# Root.net
KiCad netlist of a schematic drawn in Altium Designer
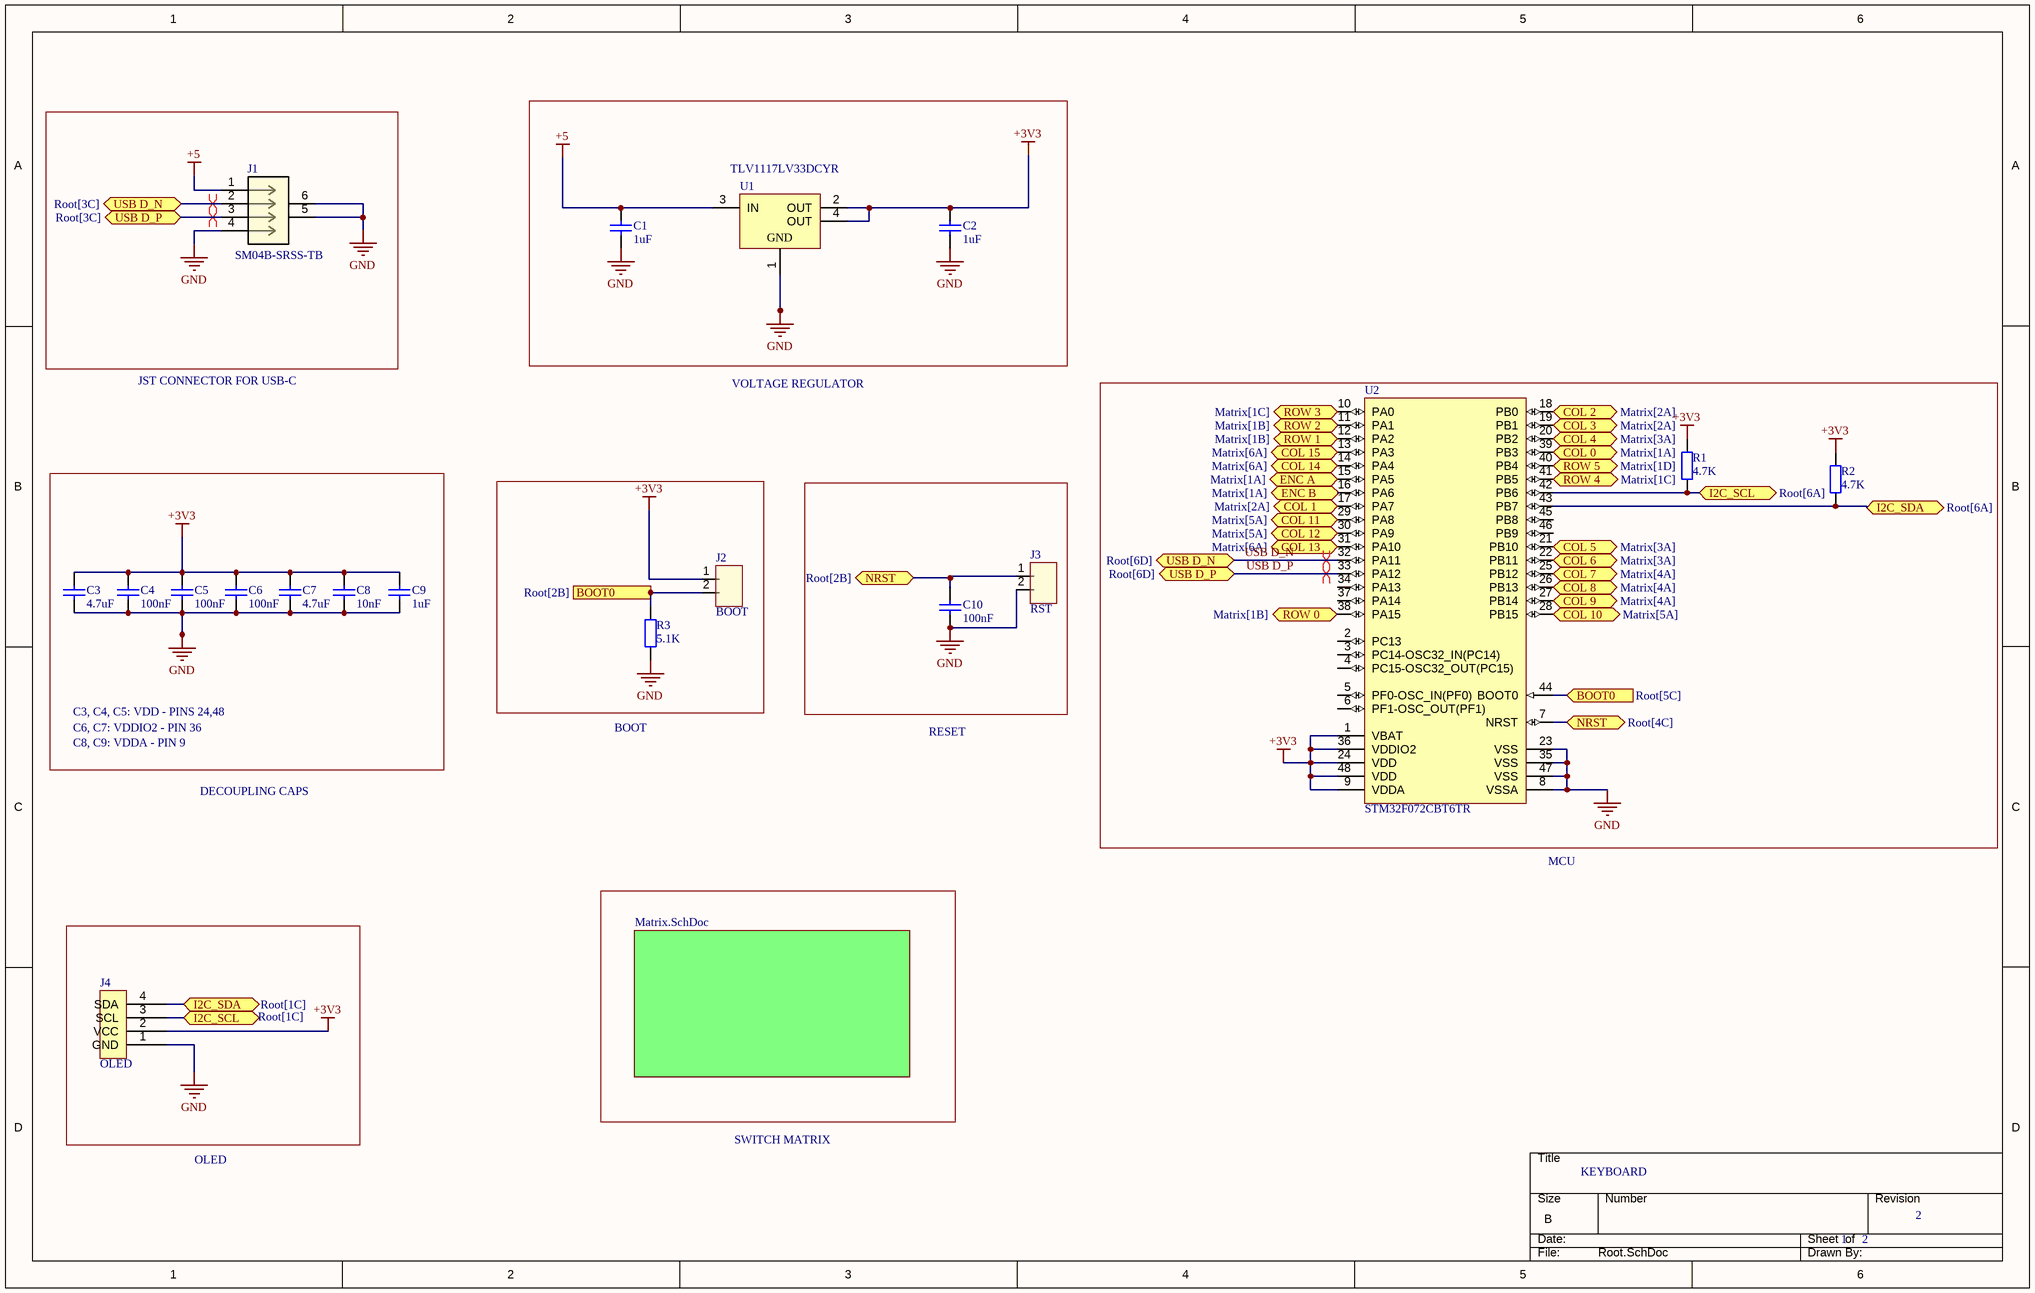
[diagram p0: Root.SchDoc]

(export (version "E")
  (design (tool "Eeschema 10.0.6"))
  (components
    (comp (ref "C1")
      (value "1uF")
      (footprint "C0805")
      (description "Capacitor")
      (fields (field (name "Comment") "Cap") (field (name "PUBLISHER") "Altium Limited"))
      (libsource (lib "Miscellaneous Devices") (part "Cap"))
    )
    (comp (ref "C2")
      (value "1uF")
      (footprint "C0805")
      (description "Capacitor")
      (fields (field (name "Comment") "Cap") (field (name "PUBLISHER") "Altium Limited"))
      (libsource (lib "Miscellaneous Devices") (part "Cap"))
    )
    (comp (ref "C3")
      (value "4.7uF")
      (footprint "C0805")
      (description "Capacitor")
      (fields (field (name "Comment") "Cap") (field (name "PUBLISHER") "Altium Limited"))
      (libsource (lib "Miscellaneous Devices") (part "Cap"))
    )
    (comp (ref "C4")
      (value "100nF")
      (footprint "C0805")
      (description "Capacitor")
      (fields (field (name "Comment") "Cap") (field (name "PUBLISHER") "Altium Limited"))
      (libsource (lib "Miscellaneous Devices") (part "Cap"))
    )
    (comp (ref "C5")
      (value "100nF")
      (footprint "C0805")
      (description "Capacitor")
      (fields (field (name "Comment") "Cap") (field (name "PUBLISHER") "Altium Limited"))
      (libsource (lib "Miscellaneous Devices") (part "Cap"))
    )
    (comp (ref "C6")
      (value "100nF")
      (footprint "C0805")
      (description "Capacitor")
      (fields (field (name "Comment") "Cap") (field (name "PUBLISHER") "Altium Limited"))
      (libsource (lib "Miscellaneous Devices") (part "Cap"))
    )
    (comp (ref "C7")
      (value "4.7uF")
      (footprint "C0805")
      (description "Capacitor")
      (fields (field (name "Comment") "Cap") (field (name "PUBLISHER") "Altium Limited"))
      (libsource (lib "Miscellaneous Devices") (part "Cap"))
    )
    (comp (ref "C8")
      (value "10nF")
      (footprint "C0805")
      (description "Capacitor")
      (fields (field (name "Comment") "Cap") (field (name "PUBLISHER") "Altium Limited"))
      (libsource (lib "Miscellaneous Devices") (part "Cap"))
    )
    (comp (ref "C9")
      (value "1uF")
      (footprint "C0805")
      (description "Capacitor")
      (fields (field (name "Comment") "Cap") (field (name "PUBLISHER") "Altium Limited"))
      (libsource (lib "Miscellaneous Devices") (part "Cap"))
    )
    (comp (ref "C10")
      (value "100nF")
      (footprint "C0805")
      (description "Capacitor")
      (fields (field (name "Comment") "Cap") (field (name "PUBLISHER") "Altium Limited"))
      (libsource (lib "Miscellaneous Devices") (part "Cap"))
    )
    (comp (ref "J1")
      (value "SM04B-SRSS-TB")
      (footprint "JST-SR-4")
      (description "No Description Available")
      (libsource (lib "SM04B-SRSS-TB") (part "SM04B-SRSS-TB"))
    )
    (comp (ref "J2")
      (value "BOOT")
      (footprint "HDR_1X2")
      (libsource (lib "Daniel Hai") (part "Copy of HDRMINI_M_1X2"))
    )
    (comp (ref "J3")
      (value "RST")
      (footprint "HDR_1X2")
      (libsource (lib "Daniel Hai") (part "Copy of HDRMINI_M_1X2"))
    )
    (comp (ref "J4")
      (value "OLED")
      (footprint "SSD1306-0.91-OLED-4pin-128x32")
      (description "4 pin header")
      (libsource (lib "Daniel Hai") (part "GND"))
    )
    (comp (ref "R1")
      (value "4.7K")
      (footprint "6-0805_M")
      (description "Resistor")
      (fields (field (name "Comment") "Res2") (field (name "PUBLISHER") "Altium Limited"))
      (libsource (lib "Miscellaneous Devices") (part "Res2"))
    )
    (comp (ref "R2")
      (value "4.7K")
      (footprint "6-0805_M")
      (description "Resistor")
      (fields (field (name "Comment") "Res2") (field (name "PUBLISHER") "Altium Limited"))
      (libsource (lib "Miscellaneous Devices") (part "Res2"))
    )
    (comp (ref "R3")
      (value "5.1K")
      (footprint "6-0805_M")
      (description "Resistor")
      (fields (field (name "Comment") "Res2") (field (name "PUBLISHER") "Altium Limited"))
      (libsource (lib "Miscellaneous Devices") (part "Res2"))
    )
    (comp (ref "U1")
      (value "TLV1117LV33DCYR")
      (footprint "DCY0004A_M")
      (fields (field (name "MANUFACTURER") "Texas Instruments"))
      (libsource (lib "Altium Content Vault") (part "TI-TLV1117LV33DCY4"))
    )
    (comp (ref "U2")
      (value "STM32F072CBT6TR")
      (footprint "STM-LQFP48_M")
      (libsource (lib "Altium Content Vault") (part "MC-ARM-STM32F07X-LQFP48"))
    )
  )
  (nets
    (net (code "1") (name "+3V3") (class "Default")
      (node (ref "C2") (pin "2") (pinfunction "2_2") (pintype "passive"))
      (node (ref "C3") (pin "2") (pinfunction "2_2") (pintype "passive"))
      (node (ref "C4") (pin "2") (pinfunction "2_2") (pintype "passive"))
      (node (ref "C5") (pin "2") (pinfunction "2_2") (pintype "passive"))
      (node (ref "C6") (pin "2") (pinfunction "2_2") (pintype "passive"))
      (node (ref "C7") (pin "2") (pinfunction "2_2") (pintype "passive"))
      (node (ref "C8") (pin "2") (pinfunction "2_2") (pintype "passive"))
      (node (ref "C9") (pin "2") (pinfunction "2_2") (pintype "passive"))
      (node (ref "J2") (pin "1") (pinfunction "1_1") (pintype "passive"))
      (node (ref "J4") (pin "2") (pinfunction "VCC_2") (pintype "passive"))
      (node (ref "R1") (pin "2") (pinfunction "2_2") (pintype "passive"))
      (node (ref "R2") (pin "2") (pinfunction "2_2") (pintype "passive"))
      (node (ref "U1") (pin "2") (pinfunction "OUT_2") (pintype "power_in"))
      (node (ref "U1") (pin "4") (pinfunction "OUT_4") (pintype "power_in"))
      (node (ref "U2") (pin "1") (pinfunction "VBAT_1") (pintype "power_in"))
      (node (ref "U2") (pin "24") (pinfunction "VDD_24") (pintype "power_in"))
      (node (ref "U2") (pin "36") (pinfunction "VDDIO2_36") (pintype "power_in"))
      (node (ref "U2") (pin "48") (pinfunction "VDD_48") (pintype "power_in"))
      (node (ref "U2") (pin "9") (pinfunction "VDDA_9") (pintype "power_in"))
    )
    (net (code "2") (name "+5") (class "Default")
      (node (ref "C1") (pin "2") (pinfunction "2_2") (pintype "passive"))
      (node (ref "J1") (pin "1") (pinfunction "1_1") (pintype "passive"))
      (node (ref "U1") (pin "3") (pinfunction "IN_3") (pintype "power_in"))
    )
    (net (code "3") (name "/BOOT0") (class "Default")
      (node (ref "J2") (pin "2") (pinfunction "2_2") (pintype "passive"))
      (node (ref "R3") (pin "2") (pinfunction "2_2") (pintype "passive"))
      (node (ref "U2") (pin "44") (pinfunction "BOOT0_44") (pintype "input"))
    )
    (net (code "4") (name "/COL 0") (class "Default")
      (node (ref "U2") (pin "39") (pinfunction "PB3_39") (pintype "bidirectional"))
    )
    (net (code "5") (name "/COL 1") (class "Default")
      (node (ref "U2") (pin "17") (pinfunction "PA7_17") (pintype "bidirectional"))
    )
    (net (code "6") (name "/COL 2") (class "Default")
      (node (ref "U2") (pin "18") (pinfunction "PB0_18") (pintype "bidirectional"))
    )
    (net (code "7") (name "/COL 3") (class "Default")
      (node (ref "U2") (pin "19") (pinfunction "PB1_19") (pintype "bidirectional"))
    )
    (net (code "8") (name "/COL 4") (class "Default")
      (node (ref "U2") (pin "20") (pinfunction "PB2_20") (pintype "bidirectional"))
    )
    (net (code "9") (name "/COL 5") (class "Default")
      (node (ref "U2") (pin "21") (pinfunction "PB10_21") (pintype "bidirectional"))
    )
    (net (code "10") (name "/COL 6") (class "Default")
      (node (ref "U2") (pin "22") (pinfunction "PB11_22") (pintype "bidirectional"))
    )
    (net (code "11") (name "/COL 7") (class "Default")
      (node (ref "U2") (pin "25") (pinfunction "PB12_25") (pintype "bidirectional"))
    )
    (net (code "12") (name "/COL 8") (class "Default")
      (node (ref "U2") (pin "26") (pinfunction "PB13_26") (pintype "bidirectional"))
    )
    (net (code "13") (name "/COL 9") (class "Default")
      (node (ref "U2") (pin "27") (pinfunction "PB14_27") (pintype "bidirectional"))
    )
    (net (code "14") (name "/COL 10") (class "Default")
      (node (ref "U2") (pin "28") (pinfunction "PB15_28") (pintype "bidirectional"))
    )
    (net (code "15") (name "/COL 11") (class "Default")
      (node (ref "U2") (pin "29") (pinfunction "PA8_29") (pintype "bidirectional"))
    )
    (net (code "16") (name "/COL 12") (class "Default")
      (node (ref "U2") (pin "30") (pinfunction "PA9_30") (pintype "bidirectional"))
    )
    (net (code "17") (name "/COL 13") (class "Default")
      (node (ref "U2") (pin "31") (pinfunction "PA10_31") (pintype "bidirectional"))
    )
    (net (code "18") (name "/COL 14") (class "Default")
      (node (ref "U2") (pin "14") (pinfunction "PA4_14") (pintype "bidirectional"))
    )
    (net (code "19") (name "/COL 15") (class "Default")
      (node (ref "U2") (pin "13") (pinfunction "PA3_13") (pintype "bidirectional"))
    )
    (net (code "20") (name "/ENC A") (class "Default")
      (node (ref "U2") (pin "15") (pinfunction "PA5_15") (pintype "bidirectional"))
    )
    (net (code "21") (name "/ENC B") (class "Default")
      (node (ref "U2") (pin "16") (pinfunction "PA6_16") (pintype "bidirectional"))
    )
    (net (code "22") (name "/I2C_SCL") (class "Default")
      (node (ref "J4") (pin "3") (pinfunction "SCL_3") (pintype "passive"))
      (node (ref "R1") (pin "1") (pinfunction "1_1") (pintype "passive"))
      (node (ref "U2") (pin "42") (pinfunction "PB6_42") (pintype "bidirectional"))
    )
    (net (code "23") (name "/I2C_SDA") (class "Default")
      (node (ref "J4") (pin "4") (pinfunction "SDA_4") (pintype "passive"))
      (node (ref "R2") (pin "1") (pinfunction "1_1") (pintype "passive"))
      (node (ref "U2") (pin "43") (pinfunction "PB7_43") (pintype "bidirectional"))
    )
    (net (code "24") (name "/NRST") (class "Default")
      (node (ref "C10") (pin "2") (pinfunction "2_2") (pintype "passive"))
      (node (ref "J3") (pin "1") (pinfunction "1_1") (pintype "passive"))
      (node (ref "U2") (pin "7") (pinfunction "NRST_7") (pintype "bidirectional"))
    )
    (net (code "25") (name "/ROW 0") (class "Default")
      (node (ref "U2") (pin "38") (pinfunction "PA15_38") (pintype "bidirectional"))
    )
    (net (code "26") (name "/ROW 1") (class "Default")
      (node (ref "U2") (pin "12") (pinfunction "PA2_12") (pintype "bidirectional"))
    )
    (net (code "27") (name "/ROW 2") (class "Default")
      (node (ref "U2") (pin "11") (pinfunction "PA1_11") (pintype "bidirectional"))
    )
    (net (code "28") (name "/ROW 3") (class "Default")
      (node (ref "U2") (pin "10") (pinfunction "PA0_10") (pintype "bidirectional"))
    )
    (net (code "29") (name "/ROW 4") (class "Default")
      (node (ref "U2") (pin "41") (pinfunction "PB5_41") (pintype "bidirectional"))
    )
    (net (code "30") (name "/ROW 5") (class "Default")
      (node (ref "U2") (pin "40") (pinfunction "PB4_40") (pintype "bidirectional"))
    )
    (net (code "31") (name "/USB D_N") (class "Default")
      (node (ref "J1") (pin "2") (pinfunction "2_2") (pintype "passive"))
      (node (ref "U2") (pin "32") (pinfunction "PA11_32") (pintype "bidirectional"))
    )
    (net (code "32") (name "/USB D_P") (class "Default")
      (node (ref "J1") (pin "3") (pinfunction "3_3") (pintype "passive"))
      (node (ref "U2") (pin "33") (pinfunction "PA12_33") (pintype "bidirectional"))
    )
    (net (code "33") (name "GND") (class "Default")
      (node (ref "C1") (pin "1") (pinfunction "1_1") (pintype "passive"))
      (node (ref "C10") (pin "1") (pinfunction "1_1") (pintype "passive"))
      (node (ref "C2") (pin "1") (pinfunction "1_1") (pintype "passive"))
      (node (ref "C3") (pin "1") (pinfunction "1_1") (pintype "passive"))
      (node (ref "C4") (pin "1") (pinfunction "1_1") (pintype "passive"))
      (node (ref "C5") (pin "1") (pinfunction "1_1") (pintype "passive"))
      (node (ref "C6") (pin "1") (pinfunction "1_1") (pintype "passive"))
      (node (ref "C7") (pin "1") (pinfunction "1_1") (pintype "passive"))
      (node (ref "C8") (pin "1") (pinfunction "1_1") (pintype "passive"))
      (node (ref "C9") (pin "1") (pinfunction "1_1") (pintype "passive"))
      (node (ref "J1") (pin "4") (pinfunction "4_4") (pintype "passive"))
      (node (ref "J1") (pin "5") (pinfunction "MOUNT_5") (pintype "passive"))
      (node (ref "J1") (pin "6") (pinfunction "MOUNT_6") (pintype "passive"))
      (node (ref "J3") (pin "2") (pinfunction "2_2") (pintype "passive"))
      (node (ref "J4") (pin "1") (pinfunction "GND_1") (pintype "passive"))
      (node (ref "R3") (pin "1") (pinfunction "1_1") (pintype "passive"))
      (node (ref "U1") (pin "1") (pinfunction "GND_1") (pintype "power_in"))
      (node (ref "U2") (pin "23") (pinfunction "VSS_23") (pintype "power_in"))
      (node (ref "U2") (pin "35") (pinfunction "VSS_35") (pintype "power_in"))
      (node (ref "U2") (pin "47") (pinfunction "VSS_47") (pintype "power_in"))
      (node (ref "U2") (pin "8") (pinfunction "VSSA_8") (pintype "power_in"))
    )
    (net (code "34") (name "unconnected-(U2-PA13-Pad34)") (class "Default")
      (node (ref "U2") (pin "34") (pinfunction "PA13_34") (pintype "bidirectional"))
    )
    (net (code "35") (name "unconnected-(U2-PA14-Pad37)") (class "Default")
      (node (ref "U2") (pin "37") (pinfunction "PA14_37") (pintype "bidirectional"))
    )
    (net (code "36") (name "unconnected-(U2-PB8-Pad45)") (class "Default")
      (node (ref "U2") (pin "45") (pinfunction "PB8_45") (pintype "bidirectional"))
    )
    (net (code "37") (name "unconnected-(U2-PB9-Pad46)") (class "Default")
      (node (ref "U2") (pin "46") (pinfunction "PB9_46") (pintype "bidirectional"))
    )
    (net (code "38") (name "unconnected-(U2-PC13-Pad2)") (class "Default")
      (node (ref "U2") (pin "2") (pinfunction "PC13_2") (pintype "bidirectional"))
    )
    (net (code "39") (name "unconnected-(U2-PC14-OSC32_IN(PC14)-Pad3)") (class "Default")
      (node (ref "U2") (pin "3") (pinfunction "PC14-OSC32_IN(PC14)_3") (pintype "bidirectional"))
    )
    (net (code "40") (name "unconnected-(U2-PC15-OSC32_OUT(PC15)-Pad4)") (class "Default")
      (node (ref "U2") (pin "4") (pinfunction "PC15-OSC32_OUT(PC15)_4") (pintype "bidirectional"))
    )
    (net (code "41") (name "unconnected-(U2-PF0-OSC_IN(PF0)-Pad5)") (class "Default")
      (node (ref "U2") (pin "5") (pinfunction "PF0-OSC_IN(PF0)_5") (pintype "bidirectional"))
    )
    (net (code "42") (name "unconnected-(U2-PF1-OSC_OUT(PF1)-Pad6)") (class "Default")
      (node (ref "U2") (pin "6") (pinfunction "PF1-OSC_OUT(PF1)_6") (pintype "bidirectional"))
    )
  )
)
